# preparedinstruments_0_bechemel_v12_KEYPA.net
KiCad netlist of a schematic drawn in EAGLE
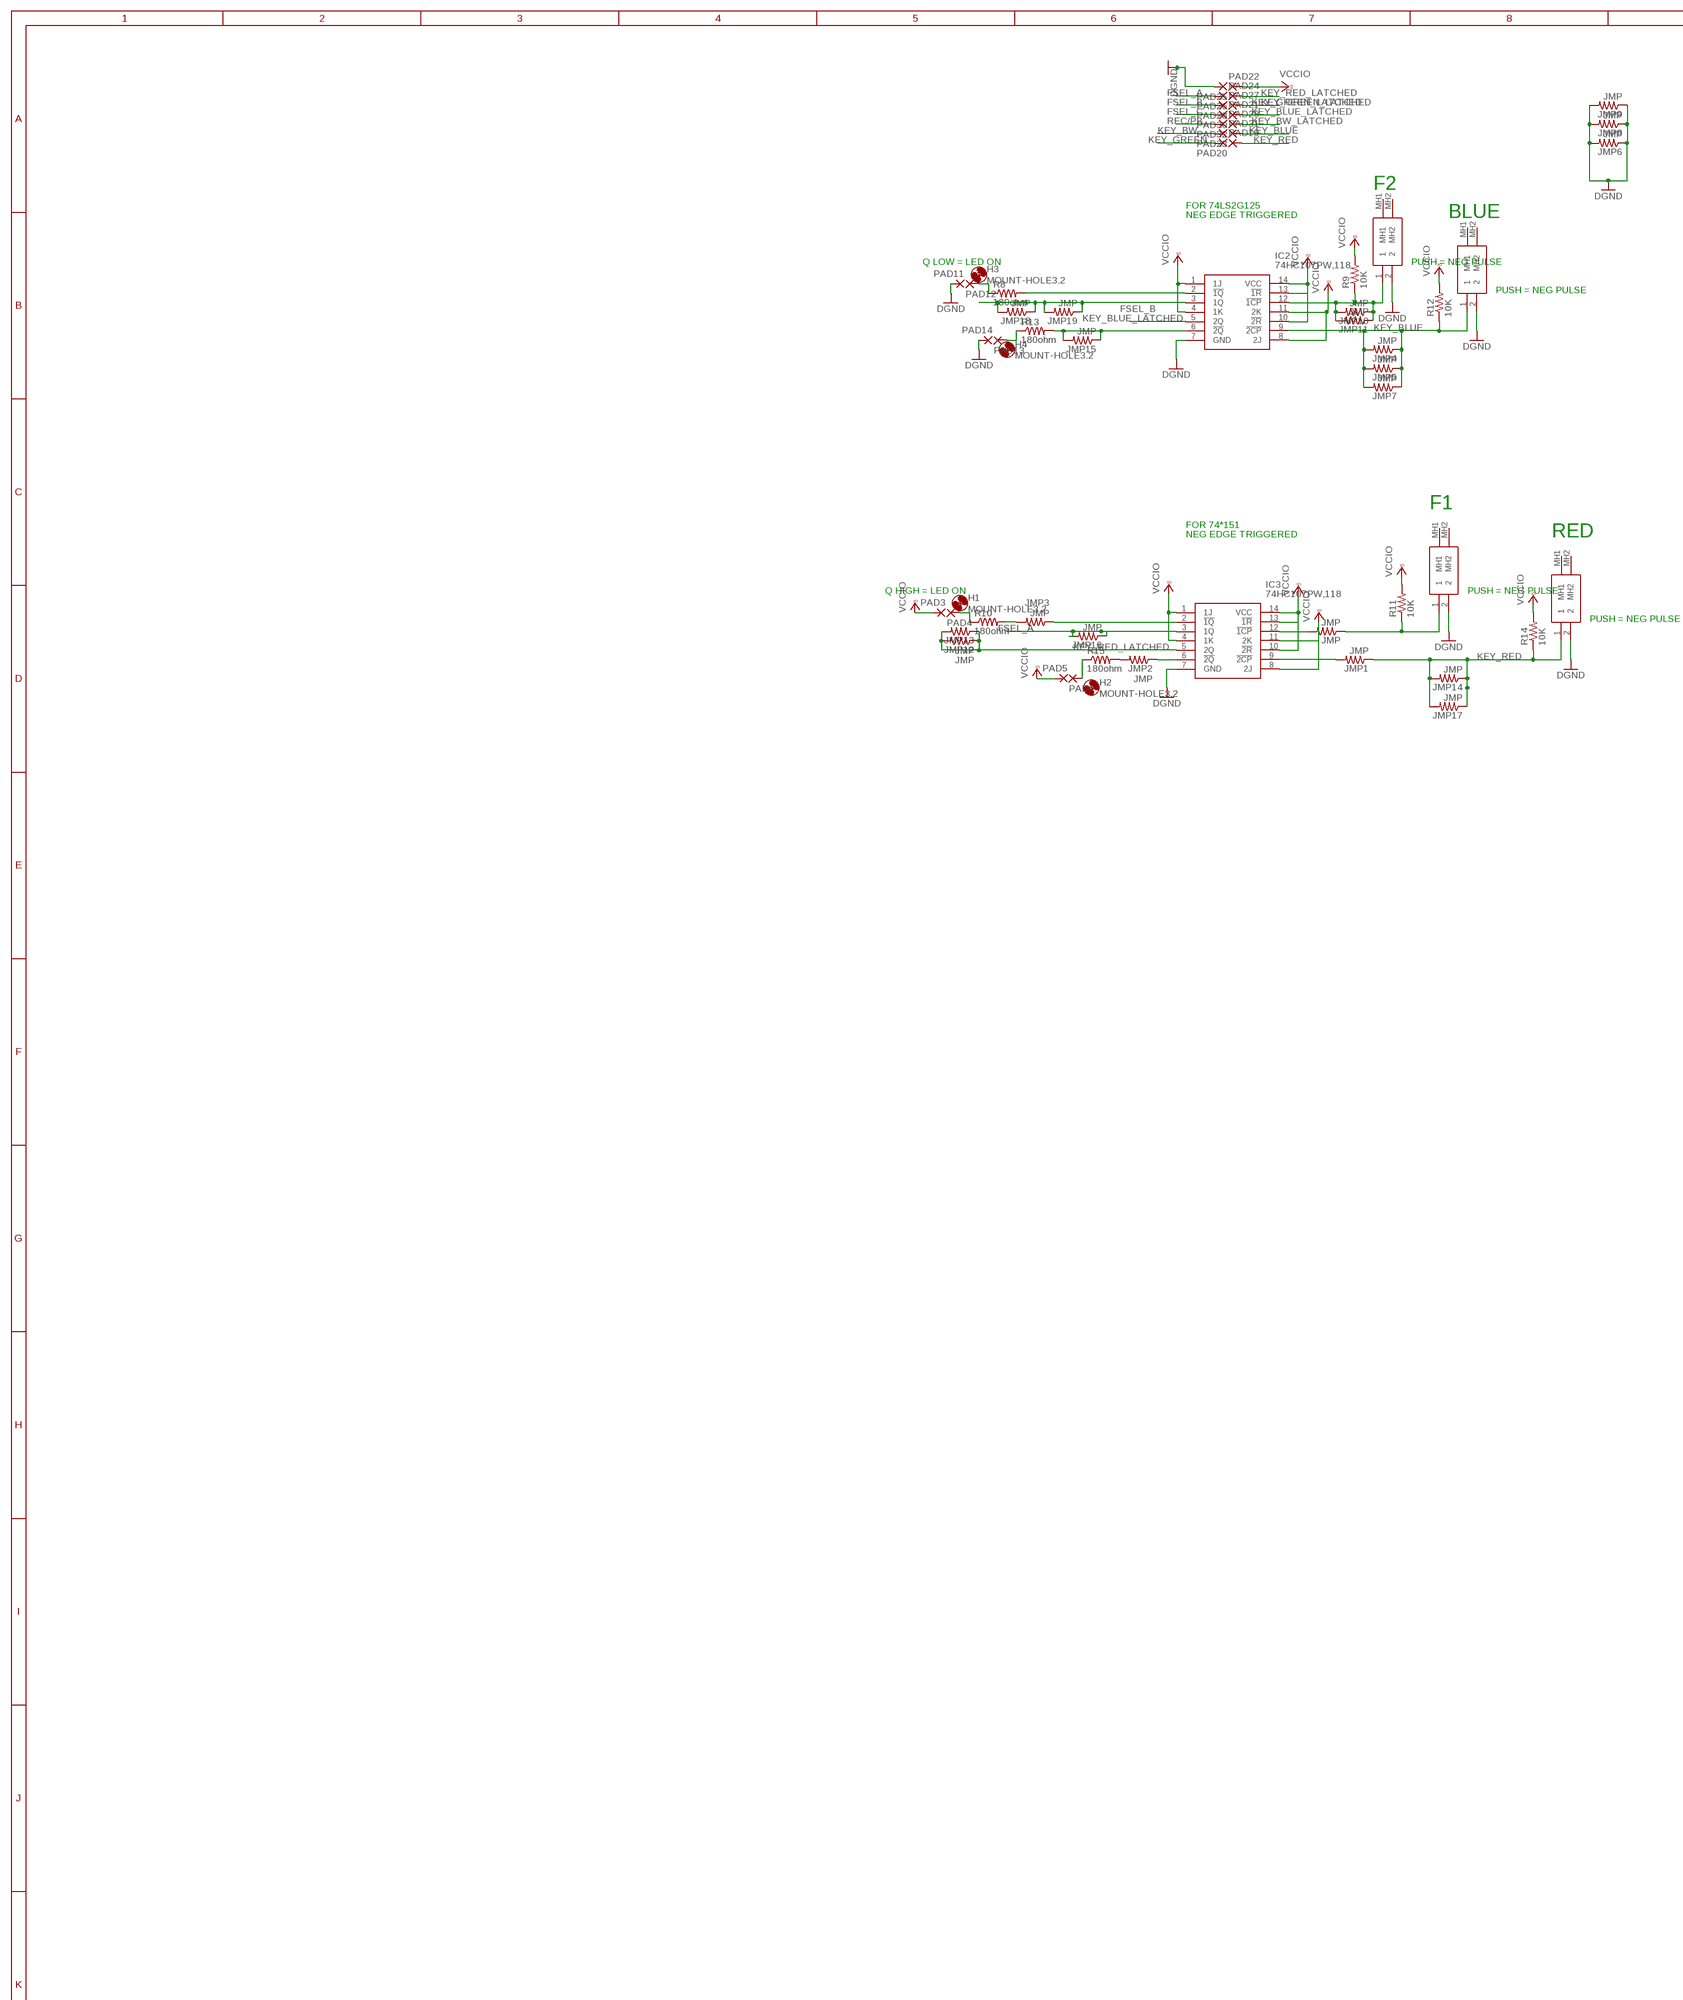
[diagram p0: schematic, sheet 1, part 1 of 3]
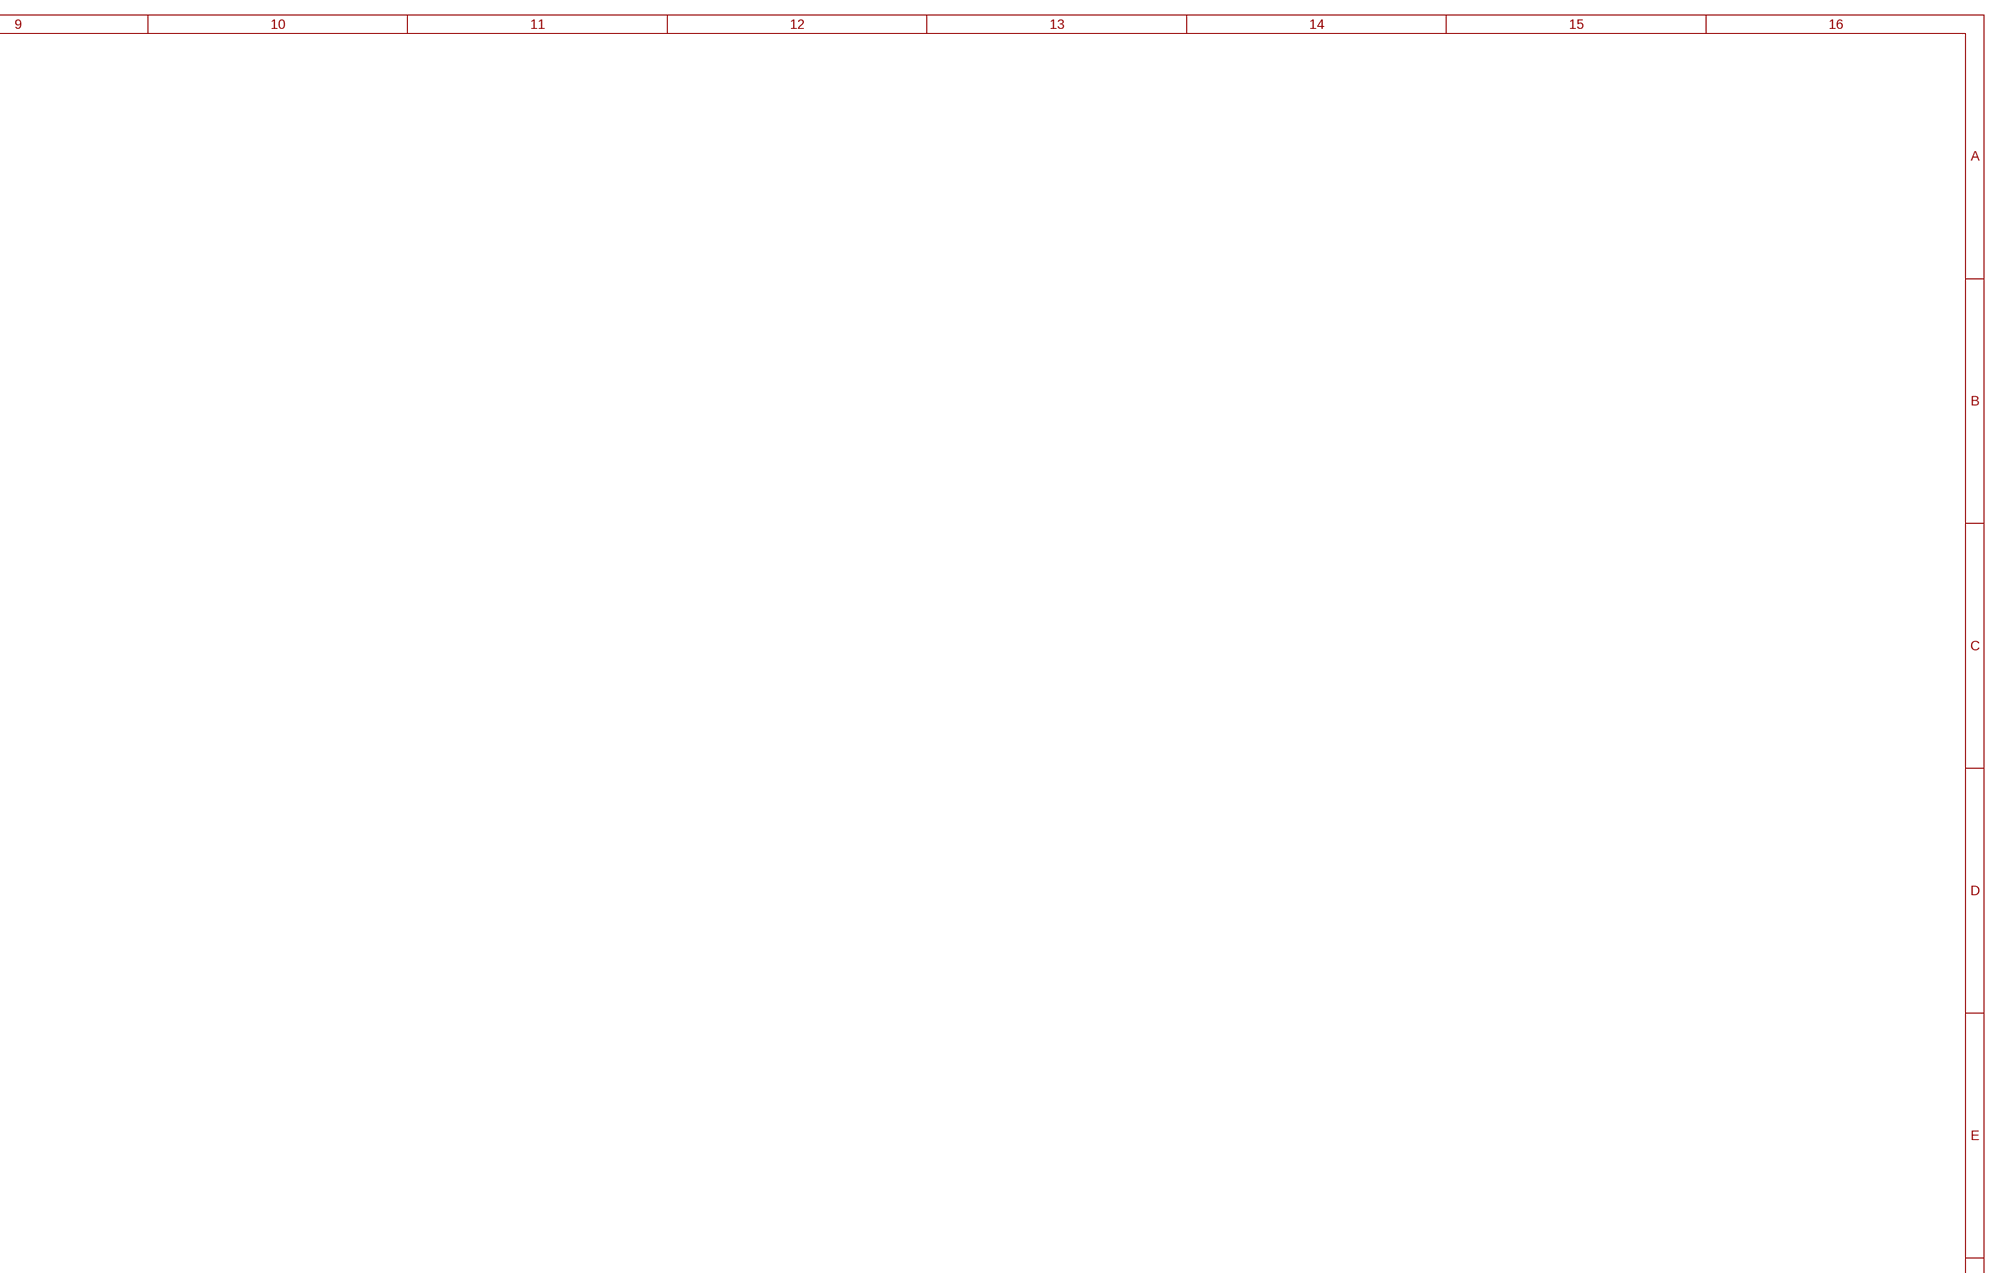
[diagram p1: schematic, sheet 1, part 2 of 3]
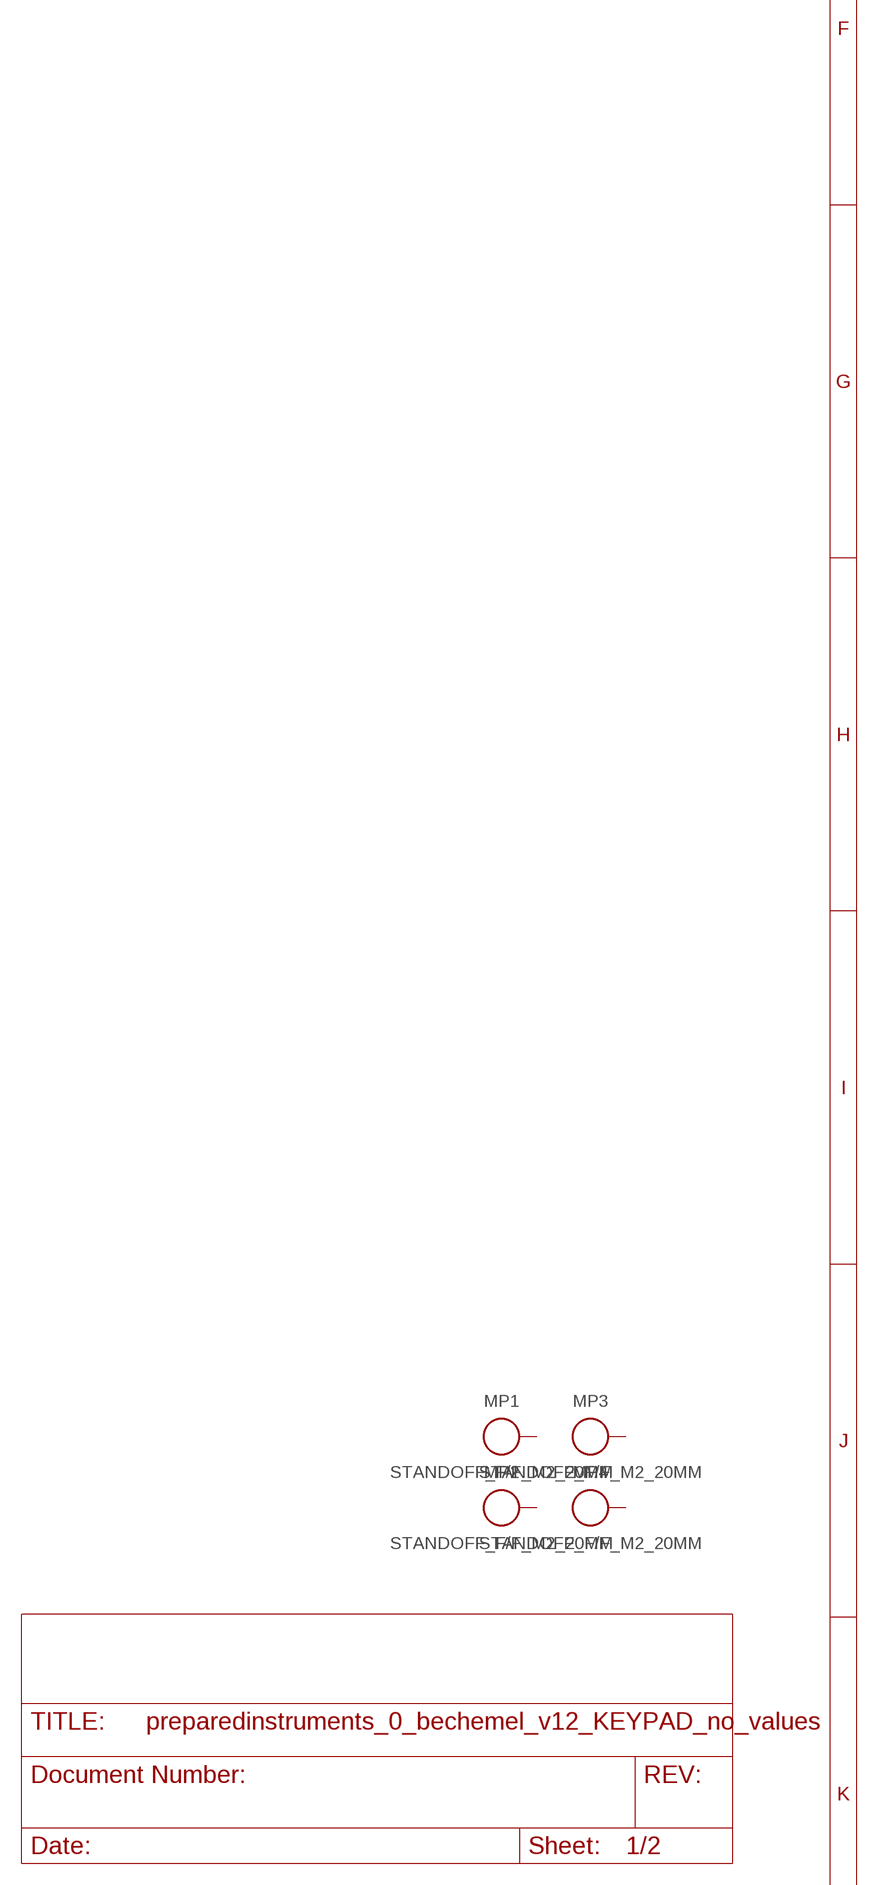
[diagram p2: schematic, sheet 1, part 3 of 3]
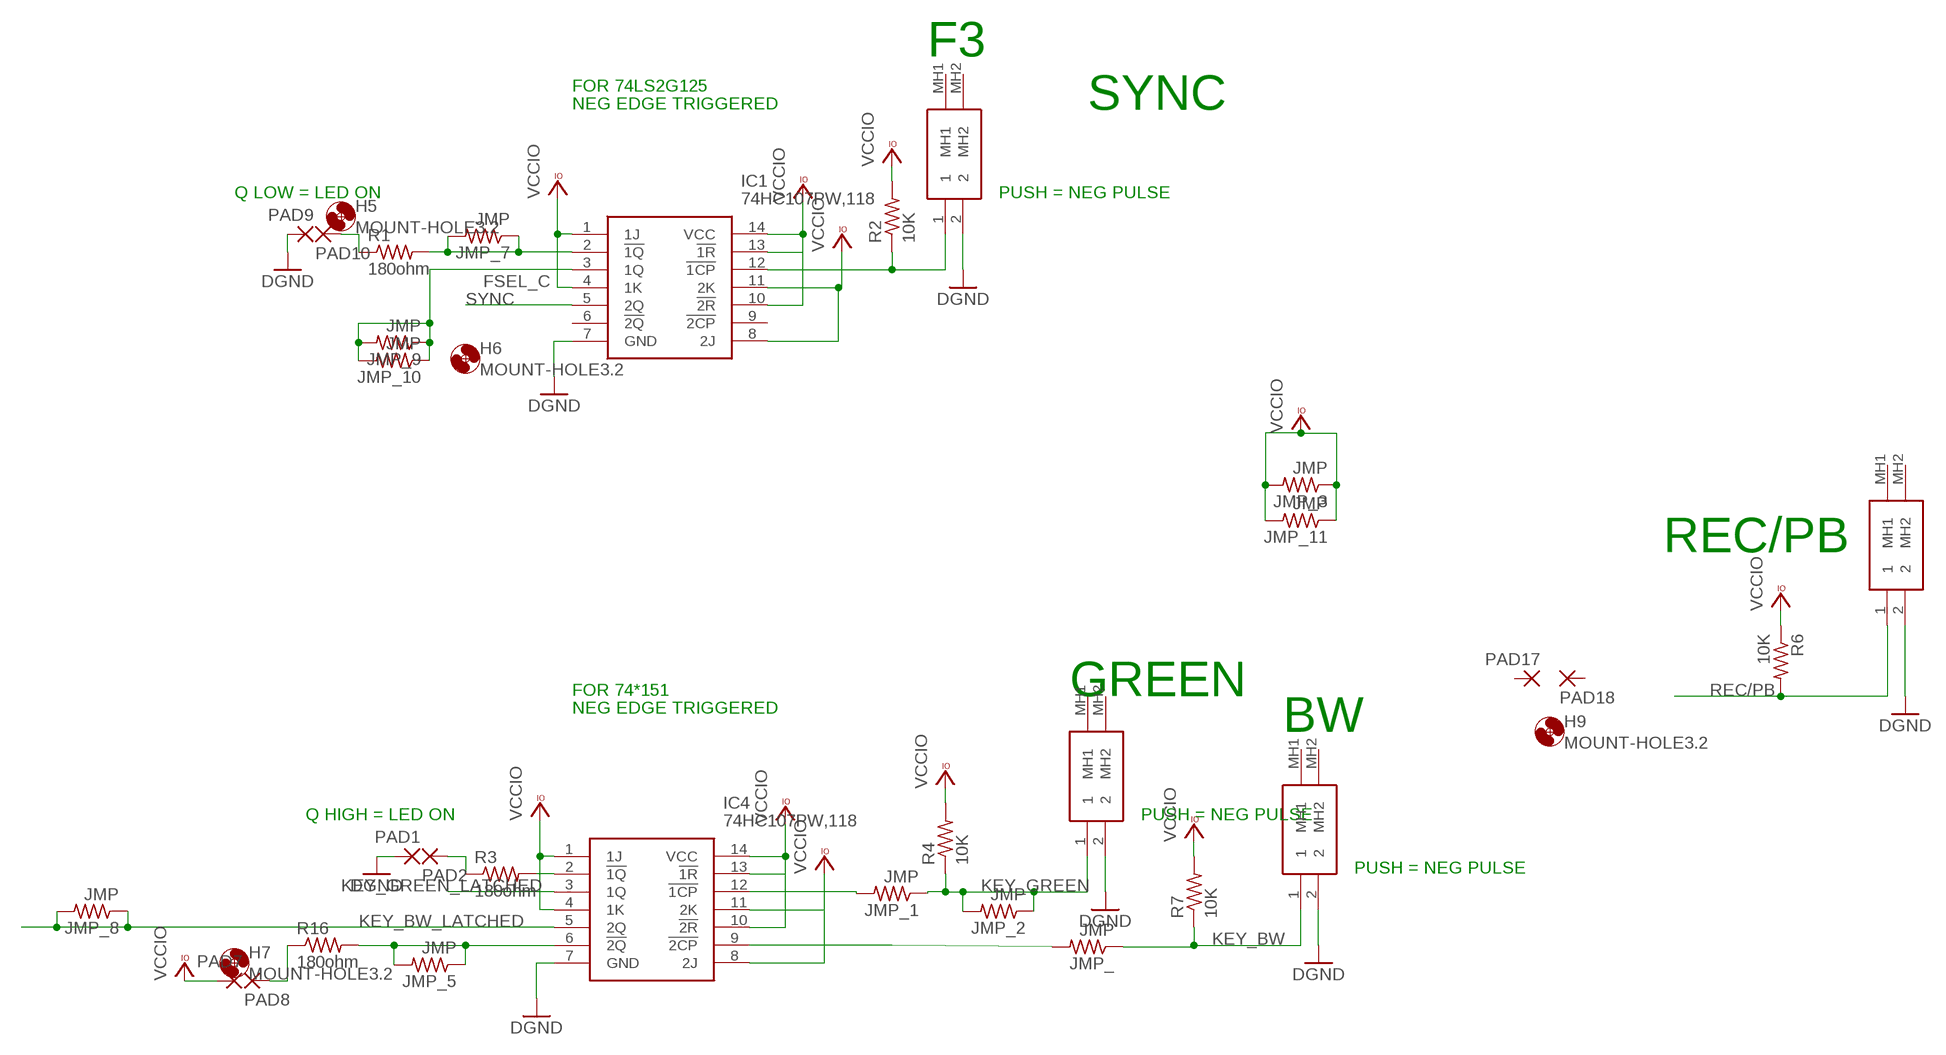
[diagram p3: schematic, sheet 2]

(export (version "E")
  (design (tool "Eeschema 10.0.6"))
  (components
    (comp (ref "H5")
      (value "MOUNT-HOLE3.2")
      (footprint "eagle-import:3,2")
      (libsource (lib "eagle-import") (part "MOUNT-HOLE3.2"))
    )
    (comp (ref "H6")
      (value "MOUNT-HOLE3.2")
      (footprint "eagle-import:3,2")
      (libsource (lib "eagle-import") (part "MOUNT-HOLE3.2"))
    )
    (comp (ref "H7")
      (value "MOUNT-HOLE3.2")
      (footprint "eagle-import:3,2")
      (libsource (lib "eagle-import") (part "MOUNT-HOLE3.2"))
    )
    (comp (ref "H9")
      (value "MOUNT-HOLE3.2")
      (footprint "eagle-import:3,2")
      (libsource (lib "eagle-import") (part "MOUNT-HOLE3.2"))
    )
    (comp (ref "IC1")
      (value "74HC107PW,118")
      (footprint "eagle-import:SOP65P640X110-14N")
      (fields (field (name "MOUSER_PART_NUMBER") "771-HC107PW118"))
      (libsource (lib "eagle-import") (part "74HC107PW,118"))
    )
    (comp (ref "IC4")
      (value "74HC107PW,118")
      (footprint "eagle-import:SOP65P640X110-14N")
      (fields (field (name "MOUSER_PART_NUMBER") "771-HC107PW118"))
      (libsource (lib "eagle-import") (part "74HC107PW,118"))
    )
    (comp (ref "JMP_")
      (value "JMP")
      (footprint "eagle-import:R0805")
      (libsource (lib "eagle-import") (part "R-US_R0805"))
    )
    (comp (ref "JMP_1")
      (value "JMP")
      (footprint "eagle-import:R0805")
      (libsource (lib "eagle-import") (part "R-US_R0805"))
    )
    (comp (ref "JMP_2")
      (value "JMP")
      (footprint "eagle-import:R0805")
      (libsource (lib "eagle-import") (part "R-US_R0805"))
    )
    (comp (ref "JMP_3")
      (value "JMP")
      (footprint "eagle-import:R0805")
      (libsource (lib "eagle-import") (part "R-US_R0805"))
    )
    (comp (ref "JMP_5")
      (value "JMP")
      (footprint "eagle-import:R0805")
      (libsource (lib "eagle-import") (part "R-US_R0805"))
    )
    (comp (ref "JMP_7")
      (value "JMP")
      (footprint "eagle-import:R0805")
      (libsource (lib "eagle-import") (part "R-US_R0805"))
    )
    (comp (ref "JMP_8")
      (value "JMP")
      (footprint "eagle-import:R0805")
      (libsource (lib "eagle-import") (part "R-US_R0805"))
    )
    (comp (ref "JMP_9")
      (value "JMP")
      (footprint "eagle-import:R0805")
      (libsource (lib "eagle-import") (part "R-US_R0805"))
    )
    (comp (ref "JMP_10")
      (value "JMP")
      (footprint "eagle-import:R0805")
      (libsource (lib "eagle-import") (part "R-US_R0805"))
    )
    (comp (ref "JMP_11")
      (value "JMP")
      (footprint "eagle-import:R0805")
      (libsource (lib "eagle-import") (part "R-US_R0805"))
    )
    (comp (ref "PAD1")
      (value "SMD2")
      (footprint "eagle-import:SMD1,27-2,54")
      (libsource (lib "eagle-import") (part "SMD2"))
    )
    (comp (ref "PAD2")
      (value "SMD2")
      (footprint "eagle-import:SMD1,27-2,54")
      (libsource (lib "eagle-import") (part "SMD2"))
    )
    (comp (ref "PAD7")
      (value "SMD2")
      (footprint "eagle-import:SMD1,27-2,54")
      (libsource (lib "eagle-import") (part "SMD2"))
    )
    (comp (ref "PAD8")
      (value "SMD2")
      (footprint "eagle-import:SMD1,27-2,54")
      (libsource (lib "eagle-import") (part "SMD2"))
    )
    (comp (ref "PAD9")
      (value "SMD2")
      (footprint "eagle-import:SMD1,27-2,54")
      (libsource (lib "eagle-import") (part "SMD2"))
    )
    (comp (ref "PAD10")
      (value "SMD2")
      (footprint "eagle-import:SMD1,27-2,54")
      (libsource (lib "eagle-import") (part "SMD2"))
    )
    (comp (ref "PAD17")
      (value "SMD2")
      (footprint "eagle-import:SMD1,27-2,54")
      (libsource (lib "eagle-import") (part "SMD2"))
    )
    (comp (ref "PAD18")
      (value "SMD2")
      (footprint "eagle-import:SMD1,27-2,54")
      (libsource (lib "eagle-import") (part "SMD2"))
    )
    (comp (ref "R1")
      (value "180ohm")
      (footprint "eagle-import:R0805")
      (libsource (lib "eagle-import") (part "R-US_R0805"))
    )
    (comp (ref "R2")
      (value "10K")
      (footprint "eagle-import:R0805")
      (libsource (lib "eagle-import") (part "R-US_R0805"))
    )
    (comp (ref "R3")
      (value "180ohm")
      (footprint "eagle-import:R0805")
      (libsource (lib "eagle-import") (part "R-US_R0805"))
    )
    (comp (ref "R4")
      (value "10K")
      (footprint "eagle-import:R0805")
      (libsource (lib "eagle-import") (part "R-US_R0805"))
    )
    (comp (ref "R6")
      (value "10K")
      (footprint "eagle-import:R0805")
      (libsource (lib "eagle-import") (part "R-US_R0805"))
    )
    (comp (ref "R7")
      (value "10K")
      (footprint "eagle-import:R0805")
      (libsource (lib "eagle-import") (part "R-US_R0805"))
    )
    (comp (ref "R16")
      (value "180ohm")
      (footprint "eagle-import:R0805")
      (libsource (lib "eagle-import") (part "R-US_R0805"))
    )
    (comp (ref "S1")
      (value "MX1A-11NW")
      (footprint "eagle-import:MX1A11NW")
      (fields (field (name "MOUSER_PART_NUMBER") "540-MX1A-11NW"))
      (libsource (lib "eagle-import") (part "MX1A-11NW"))
    )
    (comp (ref "S2")
      (value "MX1A-11NW")
      (footprint "eagle-import:MX1A11NW")
      (fields (field (name "MOUSER_PART_NUMBER") "540-MX1A-11NW"))
      (libsource (lib "eagle-import") (part "MX1A-11NW"))
    )
    (comp (ref "S4")
      (value "MX1A-11NW")
      (footprint "eagle-import:MX1A11NW")
      (fields (field (name "MOUSER_PART_NUMBER") "540-MX1A-11NW"))
      (libsource (lib "eagle-import") (part "MX1A-11NW"))
    )
    (comp (ref "S5")
      (value "MX1A-11NW")
      (footprint "eagle-import:MX1A11NW")
      (fields (field (name "MOUSER_PART_NUMBER") "540-MX1A-11NW"))
      (libsource (lib "eagle-import") (part "MX1A-11NW"))
    )
    (comp (ref "H1")
      (value "MOUNT-HOLE3.2")
      (footprint "eagle-import:3,2")
      (libsource (lib "eagle-import") (part "MOUNT-HOLE3.2"))
    )
    (comp (ref "H2")
      (value "MOUNT-HOLE3.2")
      (footprint "eagle-import:3,2")
      (libsource (lib "eagle-import") (part "MOUNT-HOLE3.2"))
    )
    (comp (ref "H3")
      (value "MOUNT-HOLE3.2")
      (footprint "eagle-import:3,2")
      (libsource (lib "eagle-import") (part "MOUNT-HOLE3.2"))
    )
    (comp (ref "H4")
      (value "MOUNT-HOLE3.2")
      (footprint "eagle-import:3,2")
      (libsource (lib "eagle-import") (part "MOUNT-HOLE3.2"))
    )
    (comp (ref "IC2")
      (value "74HC107PW,118")
      (footprint "eagle-import:SOP65P640X110-14N")
      (fields (field (name "MOUSER_PART_NUMBER") "771-HC107PW118"))
      (libsource (lib "eagle-import") (part "74HC107PW,118"))
    )
    (comp (ref "IC3")
      (value "74HC107PW,118")
      (footprint "eagle-import:SOP65P640X110-14N")
      (fields (field (name "MOUSER_PART_NUMBER") "771-HC107PW118"))
      (libsource (lib "eagle-import") (part "74HC107PW,118"))
    )
    (comp (ref "JMP")
      (value "JMP")
      (footprint "eagle-import:R0805")
      (libsource (lib "eagle-import") (part "R-US_R0805"))
    )
    (comp (ref "JMP1")
      (value "JMP")
      (footprint "eagle-import:R0805")
      (libsource (lib "eagle-import") (part "R-US_R0805"))
    )
    (comp (ref "JMP2")
      (value "JMP")
      (footprint "eagle-import:R0805")
      (libsource (lib "eagle-import") (part "R-US_R0805"))
    )
    (comp (ref "JMP3")
      (value "JMP")
      (footprint "eagle-import:R0805")
      (libsource (lib "eagle-import") (part "R-US_R0805"))
    )
    (comp (ref "JMP4")
      (value "JMP")
      (footprint "eagle-import:R0805")
      (libsource (lib "eagle-import") (part "R-US_R0805"))
    )
    (comp (ref "JMP5")
      (value "JMP")
      (footprint "eagle-import:R0805")
      (libsource (lib "eagle-import") (part "R-US_R0805"))
    )
    (comp (ref "JMP6")
      (value "JMP")
      (footprint "eagle-import:R0805")
      (libsource (lib "eagle-import") (part "R-US_R0805"))
    )
    (comp (ref "JMP7")
      (value "JMP")
      (footprint "eagle-import:R0805")
      (libsource (lib "eagle-import") (part "R-US_R0805"))
    )
    (comp (ref "JMP8")
      (value "JMP")
      (footprint "eagle-import:R0805")
      (libsource (lib "eagle-import") (part "R-US_R0805"))
    )
    (comp (ref "JMP9")
      (value "JMP")
      (footprint "eagle-import:R0805")
      (libsource (lib "eagle-import") (part "R-US_R0805"))
    )
    (comp (ref "JMP10")
      (value "JMP")
      (footprint "eagle-import:R0805")
      (libsource (lib "eagle-import") (part "R-US_R0805"))
    )
    (comp (ref "JMP11")
      (value "JMP")
      (footprint "eagle-import:R0805")
      (libsource (lib "eagle-import") (part "R-US_R0805"))
    )
    (comp (ref "JMP12")
      (value "JMP")
      (footprint "eagle-import:R0805")
      (libsource (lib "eagle-import") (part "R-US_R0805"))
    )
    (comp (ref "JMP13")
      (value "JMP")
      (footprint "eagle-import:R0805")
      (libsource (lib "eagle-import") (part "R-US_R0805"))
    )
    (comp (ref "JMP14")
      (value "JMP")
      (footprint "eagle-import:R0805")
      (libsource (lib "eagle-import") (part "R-US_R0805"))
    )
    (comp (ref "JMP15")
      (value "JMP")
      (footprint "eagle-import:R0805")
      (libsource (lib "eagle-import") (part "R-US_R0805"))
    )
    (comp (ref "JMP16")
      (value "JMP")
      (footprint "eagle-import:R0805")
      (libsource (lib "eagle-import") (part "R-US_R0805"))
    )
    (comp (ref "JMP17")
      (value "JMP")
      (footprint "eagle-import:R0805")
      (libsource (lib "eagle-import") (part "R-US_R0805"))
    )
    (comp (ref "JMP18")
      (value "JMP")
      (footprint "eagle-import:R0805")
      (libsource (lib "eagle-import") (part "R-US_R0805"))
    )
    (comp (ref "JMP19")
      (value "JMP")
      (footprint "eagle-import:R0805")
      (libsource (lib "eagle-import") (part "R-US_R0805"))
    )
    (comp (ref "MP1")
      (value "STANDOFF_F/F_M2_20MM")
      (footprint "eagle-import:STANDOFF_HEX_FEMALE_400X2000_M2X0.4_MTGP600H220")
      (libsource (lib "eagle-import") (part "STANDOFF_F/FM2_20MM_"))
    )
    (comp (ref "MP2")
      (value "STANDOFF_F/F_M2_20MM")
      (footprint "eagle-import:STANDOFF_HEX_FEMALE_400X2000_M2X0.4_MTGP600H220")
      (libsource (lib "eagle-import") (part "STANDOFF_F/FM2_20MM_"))
    )
    (comp (ref "MP3")
      (value "STANDOFF_F/F_M2_20MM")
      (footprint "eagle-import:STANDOFF_HEX_FEMALE_400X2000_M2X0.4_MTGP600H220")
      (libsource (lib "eagle-import") (part "STANDOFF_F/FM2_20MM_"))
    )
    (comp (ref "MP4")
      (value "STANDOFF_F/F_M2_20MM")
      (footprint "eagle-import:STANDOFF_HEX_FEMALE_400X2000_M2X0.4_MTGP600H220")
      (libsource (lib "eagle-import") (part "STANDOFF_F/FM2_20MM_"))
    )
    (comp (ref "PAD3")
      (value "SMD2")
      (footprint "eagle-import:SMD1,27-2,54")
      (libsource (lib "eagle-import") (part "SMD2"))
    )
    (comp (ref "PAD4")
      (value "SMD2")
      (footprint "eagle-import:SMD1,27-2,54")
      (libsource (lib "eagle-import") (part "SMD2"))
    )
    (comp (ref "PAD5")
      (value "SMD2")
      (footprint "eagle-import:SMD1,27-2,54")
      (libsource (lib "eagle-import") (part "SMD2"))
    )
    (comp (ref "PAD6")
      (value "SMD2")
      (footprint "eagle-import:SMD1,27-2,54")
      (libsource (lib "eagle-import") (part "SMD2"))
    )
    (comp (ref "PAD11")
      (value "SMD2")
      (footprint "eagle-import:SMD1,27-2,54")
      (libsource (lib "eagle-import") (part "SMD2"))
    )
    (comp (ref "PAD12")
      (value "SMD2")
      (footprint "eagle-import:SMD1,27-2,54")
      (libsource (lib "eagle-import") (part "SMD2"))
    )
    (comp (ref "PAD13")
      (value "SMD2")
      (footprint "eagle-import:SMD1,27-2,54")
      (libsource (lib "eagle-import") (part "SMD2"))
    )
    (comp (ref "PAD14")
      (value "SMD2")
      (footprint "eagle-import:SMD1,27-2,54")
      (libsource (lib "eagle-import") (part "SMD2"))
    )
    (comp (ref "PAD19")
      (value "SMD2")
      (footprint "eagle-import:SMD1,27-2,54")
      (libsource (lib "eagle-import") (part "SMD2"))
    )
    (comp (ref "PAD20")
      (value "SMD2")
      (footprint "eagle-import:SMD1,27-2,54")
      (libsource (lib "eagle-import") (part "SMD2"))
    )
    (comp (ref "PAD21")
      (value "SMD2")
      (footprint "eagle-import:SMD1,27-2,54")
      (libsource (lib "eagle-import") (part "SMD2"))
    )
    (comp (ref "PAD22")
      (value "SMD2")
      (footprint "eagle-import:SMD1,27-2,54")
      (libsource (lib "eagle-import") (part "SMD2"))
    )
    (comp (ref "PAD23")
      (value "SMD2")
      (footprint "eagle-import:SMD1,27-2,54")
      (libsource (lib "eagle-import") (part "SMD2"))
    )
    (comp (ref "PAD24")
      (value "SMD2")
      (footprint "eagle-import:SMD1,27-2,54")
      (libsource (lib "eagle-import") (part "SMD2"))
    )
    (comp (ref "PAD25")
      (value "SMD2")
      (footprint "eagle-import:SMD1,27-2,54")
      (libsource (lib "eagle-import") (part "SMD2"))
    )
    (comp (ref "PAD26")
      (value "SMD2")
      (footprint "eagle-import:SMD1,27-2,54")
      (libsource (lib "eagle-import") (part "SMD2"))
    )
    (comp (ref "PAD27")
      (value "SMD2")
      (footprint "eagle-import:SMD1,27-2,54")
      (libsource (lib "eagle-import") (part "SMD2"))
    )
    (comp (ref "PAD28")
      (value "SMD2")
      (footprint "eagle-import:SMD1,27-2,54")
      (libsource (lib "eagle-import") (part "SMD2"))
    )
    (comp (ref "PAD29")
      (value "SMD2")
      (footprint "eagle-import:SMD1,27-2,54")
      (libsource (lib "eagle-import") (part "SMD2"))
    )
    (comp (ref "PAD30")
      (value "SMD2")
      (footprint "eagle-import:SMD1,27-2,54")
      (libsource (lib "eagle-import") (part "SMD2"))
    )
    (comp (ref "PAD31")
      (value "SMD2")
      (footprint "eagle-import:SMD1,27-2,54")
      (libsource (lib "eagle-import") (part "SMD2"))
    )
    (comp (ref "PAD32")
      (value "SMD2")
      (footprint "eagle-import:SMD1,27-2,54")
      (libsource (lib "eagle-import") (part "SMD2"))
    )
    (comp (ref "R8")
      (value "180ohm")
      (footprint "eagle-import:R0805")
      (libsource (lib "eagle-import") (part "R-US_R0805"))
    )
    (comp (ref "R9")
      (value "10K")
      (footprint "eagle-import:R0805")
      (libsource (lib "eagle-import") (part "R-US_R0805"))
    )
    (comp (ref "R10")
      (value "180ohm")
      (footprint "eagle-import:R0805")
      (libsource (lib "eagle-import") (part "R-US_R0805"))
    )
    (comp (ref "R11")
      (value "10K")
      (footprint "eagle-import:R0805")
      (libsource (lib "eagle-import") (part "R-US_R0805"))
    )
    (comp (ref "R12")
      (value "10K")
      (footprint "eagle-import:R0805")
      (libsource (lib "eagle-import") (part "R-US_R0805"))
    )
    (comp (ref "R13")
      (value "180ohm")
      (footprint "eagle-import:R0805")
      (libsource (lib "eagle-import") (part "R-US_R0805"))
    )
    (comp (ref "R14")
      (value "10K")
      (footprint "eagle-import:R0805")
      (libsource (lib "eagle-import") (part "R-US_R0805"))
    )
    (comp (ref "R15")
      (value "180ohm")
      (footprint "eagle-import:R0805")
      (libsource (lib "eagle-import") (part "R-US_R0805"))
    )
    (comp (ref "S6")
      (value "MX1A-11NW")
      (footprint "eagle-import:MX1A11NW")
      (fields (field (name "MOUSER_PART_NUMBER") "540-MX1A-11NW"))
      (libsource (lib "eagle-import") (part "MX1A-11NW"))
    )
    (comp (ref "S7")
      (value "MX1A-11NW")
      (footprint "eagle-import:MX1A11NW")
      (fields (field (name "MOUSER_PART_NUMBER") "540-MX1A-11NW"))
      (libsource (lib "eagle-import") (part "MX1A-11NW"))
    )
    (comp (ref "S8")
      (value "MX1A-11NW")
      (footprint "eagle-import:MX1A11NW")
      (fields (field (name "MOUSER_PART_NUMBER") "540-MX1A-11NW"))
      (libsource (lib "eagle-import") (part "MX1A-11NW"))
    )
    (comp (ref "S9")
      (value "MX1A-11NW")
      (footprint "eagle-import:MX1A11NW")
      (fields (field (name "MOUSER_PART_NUMBER") "540-MX1A-11NW"))
      (libsource (lib "eagle-import") (part "MX1A-11NW"))
    )
  )
  (nets
    (net (code "1") (name "DGND") (class "Default")
      (node (ref "IC1") (pin "7") (pinfunction "GND_7") (pintype "bidirectional"))
      (node (ref "IC2") (pin "7") (pinfunction "GND_7") (pintype "bidirectional"))
      (node (ref "IC3") (pin "7") (pinfunction "GND_7") (pintype "bidirectional"))
      (node (ref "IC4") (pin "7") (pinfunction "GND_7") (pintype "bidirectional"))
      (node (ref "JMP6") (pin "1") (pinfunction "1_1") (pintype "passive"))
      (node (ref "JMP6") (pin "2") (pinfunction "2_2") (pintype "passive"))
      (node (ref "JMP8") (pin "1") (pinfunction "1_1") (pintype "passive"))
      (node (ref "JMP8") (pin "2") (pinfunction "2_2") (pintype "passive"))
      (node (ref "JMP9") (pin "1") (pinfunction "1_1") (pintype "passive"))
      (node (ref "JMP9") (pin "2") (pinfunction "2_2") (pintype "passive"))
      (node (ref "PAD1") (pin "1") (pinfunction "P_1") (pintype "passive"))
      (node (ref "PAD11") (pin "1") (pinfunction "P_1") (pintype "passive"))
      (node (ref "PAD14") (pin "1") (pinfunction "P_1") (pintype "passive"))
      (node (ref "PAD25") (pin "1") (pinfunction "P_1") (pintype "passive"))
      (node (ref "PAD9") (pin "1") (pinfunction "P_1") (pintype "passive"))
      (node (ref "S1") (pin "2") (pinfunction "2_2") (pintype "bidirectional"))
      (node (ref "S2") (pin "2") (pinfunction "2_2") (pintype "bidirectional"))
      (node (ref "S4") (pin "2") (pinfunction "2_2") (pintype "bidirectional"))
      (node (ref "S5") (pin "2") (pinfunction "2_2") (pintype "bidirectional"))
      (node (ref "S6") (pin "2") (pinfunction "2_2") (pintype "bidirectional"))
      (node (ref "S7") (pin "2") (pinfunction "2_2") (pintype "bidirectional"))
      (node (ref "S8") (pin "2") (pinfunction "2_2") (pintype "bidirectional"))
      (node (ref "S9") (pin "2") (pinfunction "2_2") (pintype "bidirectional"))
    )
    (net (code "2") (name "FSEL_A") (class "Default")
      (node (ref "IC3") (pin "3") (pinfunction "1Q_3") (pintype "bidirectional"))
      (node (ref "JMP16") (pin "1") (pinfunction "1_1") (pintype "passive"))
      (node (ref "JMP16") (pin "2") (pinfunction "2_2") (pintype "passive"))
      (node (ref "PAD26") (pin "1") (pinfunction "P_1") (pintype "passive"))
    )
    (net (code "3") (name "FSEL_B") (class "Default")
      (node (ref "IC2") (pin "3") (pinfunction "1Q_3") (pintype "bidirectional"))
      (node (ref "JMP18") (pin "1") (pinfunction "1_1") (pintype "passive"))
      (node (ref "JMP18") (pin "2") (pinfunction "2_2") (pintype "passive"))
      (node (ref "JMP19") (pin "1") (pinfunction "1_1") (pintype "passive"))
      (node (ref "JMP19") (pin "2") (pinfunction "2_2") (pintype "passive"))
      (node (ref "PAD28") (pin "1") (pinfunction "P_1") (pintype "passive"))
    )
    (net (code "4") (name "FSEL_C") (class "Default")
      (node (ref "IC1") (pin "3") (pinfunction "1Q_3") (pintype "bidirectional"))
      (node (ref "JMP_10") (pin "1") (pinfunction "1_1") (pintype "passive"))
      (node (ref "JMP_10") (pin "2") (pinfunction "2_2") (pintype "passive"))
      (node (ref "JMP_9") (pin "1") (pinfunction "1_1") (pintype "passive"))
      (node (ref "JMP_9") (pin "2") (pinfunction "2_2") (pintype "passive"))
      (node (ref "PAD30") (pin "1") (pinfunction "P_1") (pintype "passive"))
    )
    (net (code "5") (name "KEY_BLUE") (class "Default")
      (node (ref "IC2") (pin "9") (pinfunction "~{2CP}_9") (pintype "bidirectional"))
      (node (ref "JMP4") (pin "1") (pinfunction "1_1") (pintype "passive"))
      (node (ref "JMP4") (pin "2") (pinfunction "2_2") (pintype "passive"))
      (node (ref "JMP5") (pin "1") (pinfunction "1_1") (pintype "passive"))
      (node (ref "JMP5") (pin "2") (pinfunction "2_2") (pintype "passive"))
      (node (ref "JMP7") (pin "1") (pinfunction "1_1") (pintype "passive"))
      (node (ref "JMP7") (pin "2") (pinfunction "2_2") (pintype "passive"))
      (node (ref "PAD31") (pin "1") (pinfunction "P_1") (pintype "passive"))
      (node (ref "R12") (pin "1") (pinfunction "1_1") (pintype "passive"))
      (node (ref "S8") (pin "1") (pinfunction "1_1") (pintype "bidirectional"))
    )
    (net (code "6") (name "KEY_BLUE_LATCHED") (class "Default")
      (node (ref "IC2") (pin "5") (pinfunction "2Q_5") (pintype "bidirectional"))
      (node (ref "PAD21") (pin "1") (pinfunction "P_1") (pintype "passive"))
    )
    (net (code "7") (name "KEY_BW") (class "Default")
      (node (ref "JMP_") (pin "1") (pinfunction "1_1") (pintype "passive"))
      (node (ref "PAD23") (pin "1") (pinfunction "P_1") (pintype "passive"))
      (node (ref "R7") (pin "1") (pinfunction "1_1") (pintype "passive"))
      (node (ref "S4") (pin "1") (pinfunction "1_1") (pintype "bidirectional"))
    )
    (net (code "8") (name "KEY_BW_LATCHED") (class "Default")
      (node (ref "IC4") (pin "5") (pinfunction "2Q_5") (pintype "bidirectional"))
      (node (ref "JMP_8") (pin "1") (pinfunction "1_1") (pintype "passive"))
      (node (ref "JMP_8") (pin "2") (pinfunction "2_2") (pintype "passive"))
      (node (ref "PAD29") (pin "1") (pinfunction "P_1") (pintype "passive"))
    )
    (net (code "9") (name "KEY_GREEN") (class "Default")
      (node (ref "JMP_1") (pin "1") (pinfunction "1_1") (pintype "passive"))
      (node (ref "JMP_2") (pin "1") (pinfunction "1_1") (pintype "passive"))
      (node (ref "JMP_2") (pin "2") (pinfunction "2_2") (pintype "passive"))
      (node (ref "PAD20") (pin "1") (pinfunction "P_1") (pintype "passive"))
      (node (ref "R4") (pin "1") (pinfunction "1_1") (pintype "passive"))
      (node (ref "S2") (pin "1") (pinfunction "1_1") (pintype "bidirectional"))
    )
    (net (code "10") (name "KEY_GREEN_LATCHED") (class "Default")
      (node (ref "IC4") (pin "3") (pinfunction "1Q_3") (pintype "bidirectional"))
      (node (ref "PAD27") (pin "1") (pinfunction "P_1") (pintype "passive"))
    )
    (net (code "11") (name "KEY_RED") (class "Default")
      (node (ref "JMP1") (pin "1") (pinfunction "1_1") (pintype "passive"))
      (node (ref "JMP14") (pin "1") (pinfunction "1_1") (pintype "passive"))
      (node (ref "JMP14") (pin "2") (pinfunction "2_2") (pintype "passive"))
      (node (ref "JMP17") (pin "1") (pinfunction "1_1") (pintype "passive"))
      (node (ref "JMP17") (pin "2") (pinfunction "2_2") (pintype "passive"))
      (node (ref "PAD19") (pin "1") (pinfunction "P_1") (pintype "passive"))
      (node (ref "R14") (pin "1") (pinfunction "1_1") (pintype "passive"))
      (node (ref "S9") (pin "1") (pinfunction "1_1") (pintype "bidirectional"))
    )
    (net (code "12") (name "KEY_RED_LATCHED") (class "Default")
      (node (ref "IC3") (pin "5") (pinfunction "2Q_5") (pintype "bidirectional"))
      (node (ref "JMP12") (pin "1") (pinfunction "1_1") (pintype "passive"))
      (node (ref "JMP12") (pin "2") (pinfunction "2_2") (pintype "passive"))
      (node (ref "JMP13") (pin "1") (pinfunction "1_1") (pintype "passive"))
      (node (ref "JMP13") (pin "2") (pinfunction "2_2") (pintype "passive"))
      (node (ref "PAD24") (pin "1") (pinfunction "P_1") (pintype "passive"))
    )
    (net (code "13") (name "Net-(IC1-~{1CP})") (class "Default")
      (node (ref "IC1") (pin "12") (pinfunction "~{1CP}_12") (pintype "bidirectional"))
      (node (ref "R2") (pin "1") (pinfunction "1_1") (pintype "passive"))
      (node (ref "S1") (pin "1") (pinfunction "1_1") (pintype "bidirectional"))
    )
    (net (code "14") (name "Net-(IC1-~{1Q})") (class "Default")
      (node (ref "IC1") (pin "2") (pinfunction "~{1Q}_2") (pintype "bidirectional"))
      (node (ref "JMP_7") (pin "1") (pinfunction "1_1") (pintype "passive"))
      (node (ref "JMP_7") (pin "2") (pinfunction "2_2") (pintype "passive"))
      (node (ref "R1") (pin "2") (pinfunction "2_2") (pintype "passive"))
    )
    (net (code "15") (name "Net-(IC2-~{1CP})") (class "Default")
      (node (ref "IC2") (pin "12") (pinfunction "~{1CP}_12") (pintype "bidirectional"))
      (node (ref "JMP10") (pin "1") (pinfunction "1_1") (pintype "passive"))
      (node (ref "JMP10") (pin "2") (pinfunction "2_2") (pintype "passive"))
      (node (ref "JMP11") (pin "1") (pinfunction "1_1") (pintype "passive"))
      (node (ref "JMP11") (pin "2") (pinfunction "2_2") (pintype "passive"))
      (node (ref "R9") (pin "1") (pinfunction "1_1") (pintype "passive"))
      (node (ref "S6") (pin "1") (pinfunction "1_1") (pintype "bidirectional"))
    )
    (net (code "16") (name "Net-(IC2-~{1Q})") (class "Default")
      (node (ref "IC2") (pin "2") (pinfunction "~{1Q}_2") (pintype "bidirectional"))
      (node (ref "R8") (pin "2") (pinfunction "2_2") (pintype "passive"))
    )
    (net (code "17") (name "Net-(IC2-~{2Q})") (class "Default")
      (node (ref "IC2") (pin "6") (pinfunction "~{2Q}_6") (pintype "bidirectional"))
      (node (ref "JMP15") (pin "1") (pinfunction "1_1") (pintype "passive"))
      (node (ref "JMP15") (pin "2") (pinfunction "2_2") (pintype "passive"))
      (node (ref "R13") (pin "2") (pinfunction "2_2") (pintype "passive"))
    )
    (net (code "18") (name "Net-(IC3-~{1CP})") (class "Default")
      (node (ref "IC3") (pin "12") (pinfunction "~{1CP}_12") (pintype "bidirectional"))
      (node (ref "JMP") (pin "2") (pinfunction "2_2") (pintype "passive"))
    )
    (net (code "19") (name "Net-(IC3-~{1Q})") (class "Default")
      (node (ref "IC3") (pin "2") (pinfunction "~{1Q}_2") (pintype "bidirectional"))
      (node (ref "JMP3") (pin "1") (pinfunction "1_1") (pintype "passive"))
    )
    (net (code "20") (name "Net-(IC3-~{2CP})") (class "Default")
      (node (ref "IC3") (pin "9") (pinfunction "~{2CP}_9") (pintype "bidirectional"))
      (node (ref "JMP1") (pin "2") (pinfunction "2_2") (pintype "passive"))
    )
    (net (code "21") (name "Net-(IC3-~{2Q})") (class "Default")
      (node (ref "IC3") (pin "6") (pinfunction "~{2Q}_6") (pintype "bidirectional"))
      (node (ref "JMP2") (pin "1") (pinfunction "1_1") (pintype "passive"))
    )
    (net (code "22") (name "Net-(IC4-~{1CP})") (class "Default")
      (node (ref "IC4") (pin "12") (pinfunction "~{1CP}_12") (pintype "bidirectional"))
      (node (ref "JMP_1") (pin "2") (pinfunction "2_2") (pintype "passive"))
    )
    (net (code "23") (name "Net-(IC4-~{1Q})") (class "Default")
      (node (ref "IC4") (pin "2") (pinfunction "~{1Q}_2") (pintype "bidirectional"))
      (node (ref "R3") (pin "2") (pinfunction "2_2") (pintype "passive"))
    )
    (net (code "24") (name "Net-(IC4-~{2CP})") (class "Default")
      (node (ref "IC4") (pin "9") (pinfunction "~{2CP}_9") (pintype "bidirectional"))
      (node (ref "JMP_") (pin "2") (pinfunction "2_2") (pintype "passive"))
    )
    (net (code "25") (name "Net-(IC4-~{2Q})") (class "Default")
      (node (ref "IC4") (pin "6") (pinfunction "~{2Q}_6") (pintype "bidirectional"))
      (node (ref "JMP_5") (pin "1") (pinfunction "1_1") (pintype "passive"))
      (node (ref "JMP_5") (pin "2") (pinfunction "2_2") (pintype "passive"))
      (node (ref "R16") (pin "2") (pinfunction "2_2") (pintype "passive"))
    )
    (net (code "26") (name "Net-(JMP-Pad1)") (class "Default")
      (node (ref "JMP") (pin "1") (pinfunction "1_1") (pintype "passive"))
      (node (ref "R11") (pin "1") (pinfunction "1_1") (pintype "passive"))
      (node (ref "S7") (pin "1") (pinfunction "1_1") (pintype "bidirectional"))
    )
    (net (code "27") (name "Net-(JMP2-Pad2)") (class "Default")
      (node (ref "JMP2") (pin "2") (pinfunction "2_2") (pintype "passive"))
      (node (ref "R15") (pin "2") (pinfunction "2_2") (pintype "passive"))
    )
    (net (code "28") (name "Net-(JMP3-Pad2)") (class "Default")
      (node (ref "JMP3") (pin "2") (pinfunction "2_2") (pintype "passive"))
      (node (ref "R10") (pin "2") (pinfunction "2_2") (pintype "passive"))
    )
    (net (code "29") (name "Net-(PAD2-P)") (class "Default")
      (node (ref "PAD2") (pin "1") (pinfunction "P_1") (pintype "passive"))
      (node (ref "R3") (pin "1") (pinfunction "1_1") (pintype "passive"))
    )
    (net (code "30") (name "Net-(PAD4-P)") (class "Default")
      (node (ref "PAD4") (pin "1") (pinfunction "P_1") (pintype "passive"))
      (node (ref "R10") (pin "1") (pinfunction "1_1") (pintype "passive"))
    )
    (net (code "31") (name "Net-(PAD6-P)") (class "Default")
      (node (ref "PAD6") (pin "1") (pinfunction "P_1") (pintype "passive"))
      (node (ref "R15") (pin "1") (pinfunction "1_1") (pintype "passive"))
    )
    (net (code "32") (name "Net-(PAD8-P)") (class "Default")
      (node (ref "PAD8") (pin "1") (pinfunction "P_1") (pintype "passive"))
      (node (ref "R16") (pin "1") (pinfunction "1_1") (pintype "passive"))
    )
    (net (code "33") (name "Net-(PAD10-P)") (class "Default")
      (node (ref "PAD10") (pin "1") (pinfunction "P_1") (pintype "passive"))
      (node (ref "R1") (pin "1") (pinfunction "1_1") (pintype "passive"))
    )
    (net (code "34") (name "Net-(PAD12-P)") (class "Default")
      (node (ref "PAD12") (pin "1") (pinfunction "P_1") (pintype "passive"))
      (node (ref "R8") (pin "1") (pinfunction "1_1") (pintype "passive"))
    )
    (net (code "35") (name "Net-(PAD13-P)") (class "Default")
      (node (ref "PAD13") (pin "1") (pinfunction "P_1") (pintype "passive"))
      (node (ref "R13") (pin "1") (pinfunction "1_1") (pintype "passive"))
    )
    (net (code "36") (name "REC{slash}PB") (class "Default")
      (node (ref "PAD32") (pin "1") (pinfunction "P_1") (pintype "passive"))
      (node (ref "R6") (pin "2") (pinfunction "2_2") (pintype "passive"))
      (node (ref "S5") (pin "1") (pinfunction "1_1") (pintype "bidirectional"))
    )
    (net (code "37") (name "SYNC") (class "Default")
      (node (ref "IC1") (pin "5") (pinfunction "2Q_5") (pintype "bidirectional"))
    )
    (net (code "38") (name "VCCIO") (class "Default")
      (node (ref "IC1") (pin "1") (pinfunction "1J_1") (pintype "bidirectional"))
      (node (ref "IC1") (pin "10") (pinfunction "~{2R}_10") (pintype "bidirectional"))
      (node (ref "IC1") (pin "11") (pinfunction "2K_11") (pintype "bidirectional"))
      (node (ref "IC1") (pin "13") (pinfunction "~{1R}_13") (pintype "bidirectional"))
      (node (ref "IC1") (pin "14") (pinfunction "VCC_14") (pintype "bidirectional"))
      (node (ref "IC1") (pin "4") (pinfunction "1K_4") (pintype "bidirectional"))
      (node (ref "IC1") (pin "8") (pinfunction "2J_8") (pintype "bidirectional"))
      (node (ref "IC2") (pin "1") (pinfunction "1J_1") (pintype "bidirectional"))
      (node (ref "IC2") (pin "10") (pinfunction "~{2R}_10") (pintype "bidirectional"))
      (node (ref "IC2") (pin "11") (pinfunction "2K_11") (pintype "bidirectional"))
      (node (ref "IC2") (pin "13") (pinfunction "~{1R}_13") (pintype "bidirectional"))
      (node (ref "IC2") (pin "14") (pinfunction "VCC_14") (pintype "bidirectional"))
      (node (ref "IC2") (pin "4") (pinfunction "1K_4") (pintype "bidirectional"))
      (node (ref "IC2") (pin "8") (pinfunction "2J_8") (pintype "bidirectional"))
      (node (ref "IC3") (pin "1") (pinfunction "1J_1") (pintype "bidirectional"))
      (node (ref "IC3") (pin "10") (pinfunction "~{2R}_10") (pintype "bidirectional"))
      (node (ref "IC3") (pin "11") (pinfunction "2K_11") (pintype "bidirectional"))
      (node (ref "IC3") (pin "13") (pinfunction "~{1R}_13") (pintype "bidirectional"))
      (node (ref "IC3") (pin "14") (pinfunction "VCC_14") (pintype "bidirectional"))
      (node (ref "IC3") (pin "4") (pinfunction "1K_4") (pintype "bidirectional"))
      (node (ref "IC3") (pin "8") (pinfunction "2J_8") (pintype "bidirectional"))
      (node (ref "IC4") (pin "1") (pinfunction "1J_1") (pintype "bidirectional"))
      (node (ref "IC4") (pin "10") (pinfunction "~{2R}_10") (pintype "bidirectional"))
      (node (ref "IC4") (pin "11") (pinfunction "2K_11") (pintype "bidirectional"))
      (node (ref "IC4") (pin "13") (pinfunction "~{1R}_13") (pintype "bidirectional"))
      (node (ref "IC4") (pin "14") (pinfunction "VCC_14") (pintype "bidirectional"))
      (node (ref "IC4") (pin "4") (pinfunction "1K_4") (pintype "bidirectional"))
      (node (ref "IC4") (pin "8") (pinfunction "2J_8") (pintype "bidirectional"))
      (node (ref "JMP_11") (pin "1") (pinfunction "1_1") (pintype "passive"))
      (node (ref "JMP_11") (pin "2") (pinfunction "2_2") (pintype "passive"))
      (node (ref "JMP_3") (pin "1") (pinfunction "1_1") (pintype "passive"))
      (node (ref "JMP_3") (pin "2") (pinfunction "2_2") (pintype "passive"))
      (node (ref "PAD22") (pin "1") (pinfunction "P_1") (pintype "passive"))
      (node (ref "PAD3") (pin "1") (pinfunction "P_1") (pintype "passive"))
      (node (ref "PAD5") (pin "1") (pinfunction "P_1") (pintype "passive"))
      (node (ref "PAD7") (pin "1") (pinfunction "P_1") (pintype "passive"))
      (node (ref "R11") (pin "2") (pinfunction "2_2") (pintype "passive"))
      (node (ref "R12") (pin "2") (pinfunction "2_2") (pintype "passive"))
      (node (ref "R14") (pin "2") (pinfunction "2_2") (pintype "passive"))
      (node (ref "R2") (pin "2") (pinfunction "2_2") (pintype "passive"))
      (node (ref "R4") (pin "2") (pinfunction "2_2") (pintype "passive"))
      (node (ref "R6") (pin "1") (pinfunction "1_1") (pintype "passive"))
      (node (ref "R7") (pin "2") (pinfunction "2_2") (pintype "passive"))
      (node (ref "R9") (pin "2") (pinfunction "2_2") (pintype "passive"))
    )
    (net (code "39") (name "unconnected-(IC1-~{2CP}-Pad9)") (class "Default")
      (node (ref "IC1") (pin "9") (pinfunction "~{2CP}_9") (pintype "bidirectional"))
    )
    (net (code "40") (name "unconnected-(IC1-~{2Q}-Pad6)") (class "Default")
      (node (ref "IC1") (pin "6") (pinfunction "~{2Q}_6") (pintype "bidirectional"))
    )
    (net (code "41") (name "unconnected-(MP1-P$1-Pad1)") (class "Default")
      (node (ref "MP1") (pin "1") (pinfunction "P$1_1") (pintype "passive"))
    )
    (net (code "42") (name "unconnected-(MP2-P$1-Pad1)") (class "Default")
      (node (ref "MP2") (pin "1") (pinfunction "P$1_1") (pintype "passive"))
    )
    (net (code "43") (name "unconnected-(MP3-P$1-Pad1)") (class "Default")
      (node (ref "MP3") (pin "1") (pinfunction "P$1_1") (pintype "passive"))
    )
    (net (code "44") (name "unconnected-(MP4-P$1-Pad1)") (class "Default")
      (node (ref "MP4") (pin "1") (pinfunction "P$1_1") (pintype "passive"))
    )
    (net (code "45") (name "unconnected-(PAD17-P-Pad1)") (class "Default")
      (node (ref "PAD17") (pin "1") (pinfunction "P_1") (pintype "passive"))
    )
    (net (code "46") (name "unconnected-(PAD18-P-Pad1)") (class "Default")
      (node (ref "PAD18") (pin "1") (pinfunction "P_1") (pintype "passive"))
    )
    (net (code "47") (name "unconnected-(S1-PadMH1)") (class "Default")
      (node (ref "S1") (pin "MH1") (pinfunction "MH1_MH1") (pintype "bidirectional"))
    )
    (net (code "48") (name "unconnected-(S1-PadMH2)") (class "Default")
      (node (ref "S1") (pin "MH2") (pinfunction "MH2_MH2") (pintype "bidirectional"))
    )
    (net (code "49") (name "unconnected-(S2-PadMH1)") (class "Default")
      (node (ref "S2") (pin "MH1") (pinfunction "MH1_MH1") (pintype "bidirectional"))
    )
    (net (code "50") (name "unconnected-(S2-PadMH2)") (class "Default")
      (node (ref "S2") (pin "MH2") (pinfunction "MH2_MH2") (pintype "bidirectional"))
    )
    (net (code "51") (name "unconnected-(S4-PadMH1)") (class "Default")
      (node (ref "S4") (pin "MH1") (pinfunction "MH1_MH1") (pintype "bidirectional"))
    )
    (net (code "52") (name "unconnected-(S4-PadMH2)") (class "Default")
      (node (ref "S4") (pin "MH2") (pinfunction "MH2_MH2") (pintype "bidirectional"))
    )
    (net (code "53") (name "unconnected-(S5-PadMH1)") (class "Default")
      (node (ref "S5") (pin "MH1") (pinfunction "MH1_MH1") (pintype "bidirectional"))
    )
    (net (code "54") (name "unconnected-(S5-PadMH2)") (class "Default")
      (node (ref "S5") (pin "MH2") (pinfunction "MH2_MH2") (pintype "bidirectional"))
    )
    (net (code "55") (name "unconnected-(S6-PadMH1)") (class "Default")
      (node (ref "S6") (pin "MH1") (pinfunction "MH1_MH1") (pintype "bidirectional"))
    )
    (net (code "56") (name "unconnected-(S6-PadMH2)") (class "Default")
      (node (ref "S6") (pin "MH2") (pinfunction "MH2_MH2") (pintype "bidirectional"))
    )
    (net (code "57") (name "unconnected-(S7-PadMH1)") (class "Default")
      (node (ref "S7") (pin "MH1") (pinfunction "MH1_MH1") (pintype "bidirectional"))
    )
    (net (code "58") (name "unconnected-(S7-PadMH2)") (class "Default")
      (node (ref "S7") (pin "MH2") (pinfunction "MH2_MH2") (pintype "bidirectional"))
    )
    (net (code "59") (name "unconnected-(S8-PadMH1)") (class "Default")
      (node (ref "S8") (pin "MH1") (pinfunction "MH1_MH1") (pintype "bidirectional"))
    )
    (net (code "60") (name "unconnected-(S8-PadMH2)") (class "Default")
      (node (ref "S8") (pin "MH2") (pinfunction "MH2_MH2") (pintype "bidirectional"))
    )
    (net (code "61") (name "unconnected-(S9-PadMH1)") (class "Default")
      (node (ref "S9") (pin "MH1") (pinfunction "MH1_MH1") (pintype "bidirectional"))
    )
    (net (code "62") (name "unconnected-(S9-PadMH2)") (class "Default")
      (node (ref "S9") (pin "MH2") (pinfunction "MH2_MH2") (pintype "bidirectional"))
    )
  )
)
